# IR2110.net
KiCad netlist of a schematic drawn in Altium Designer
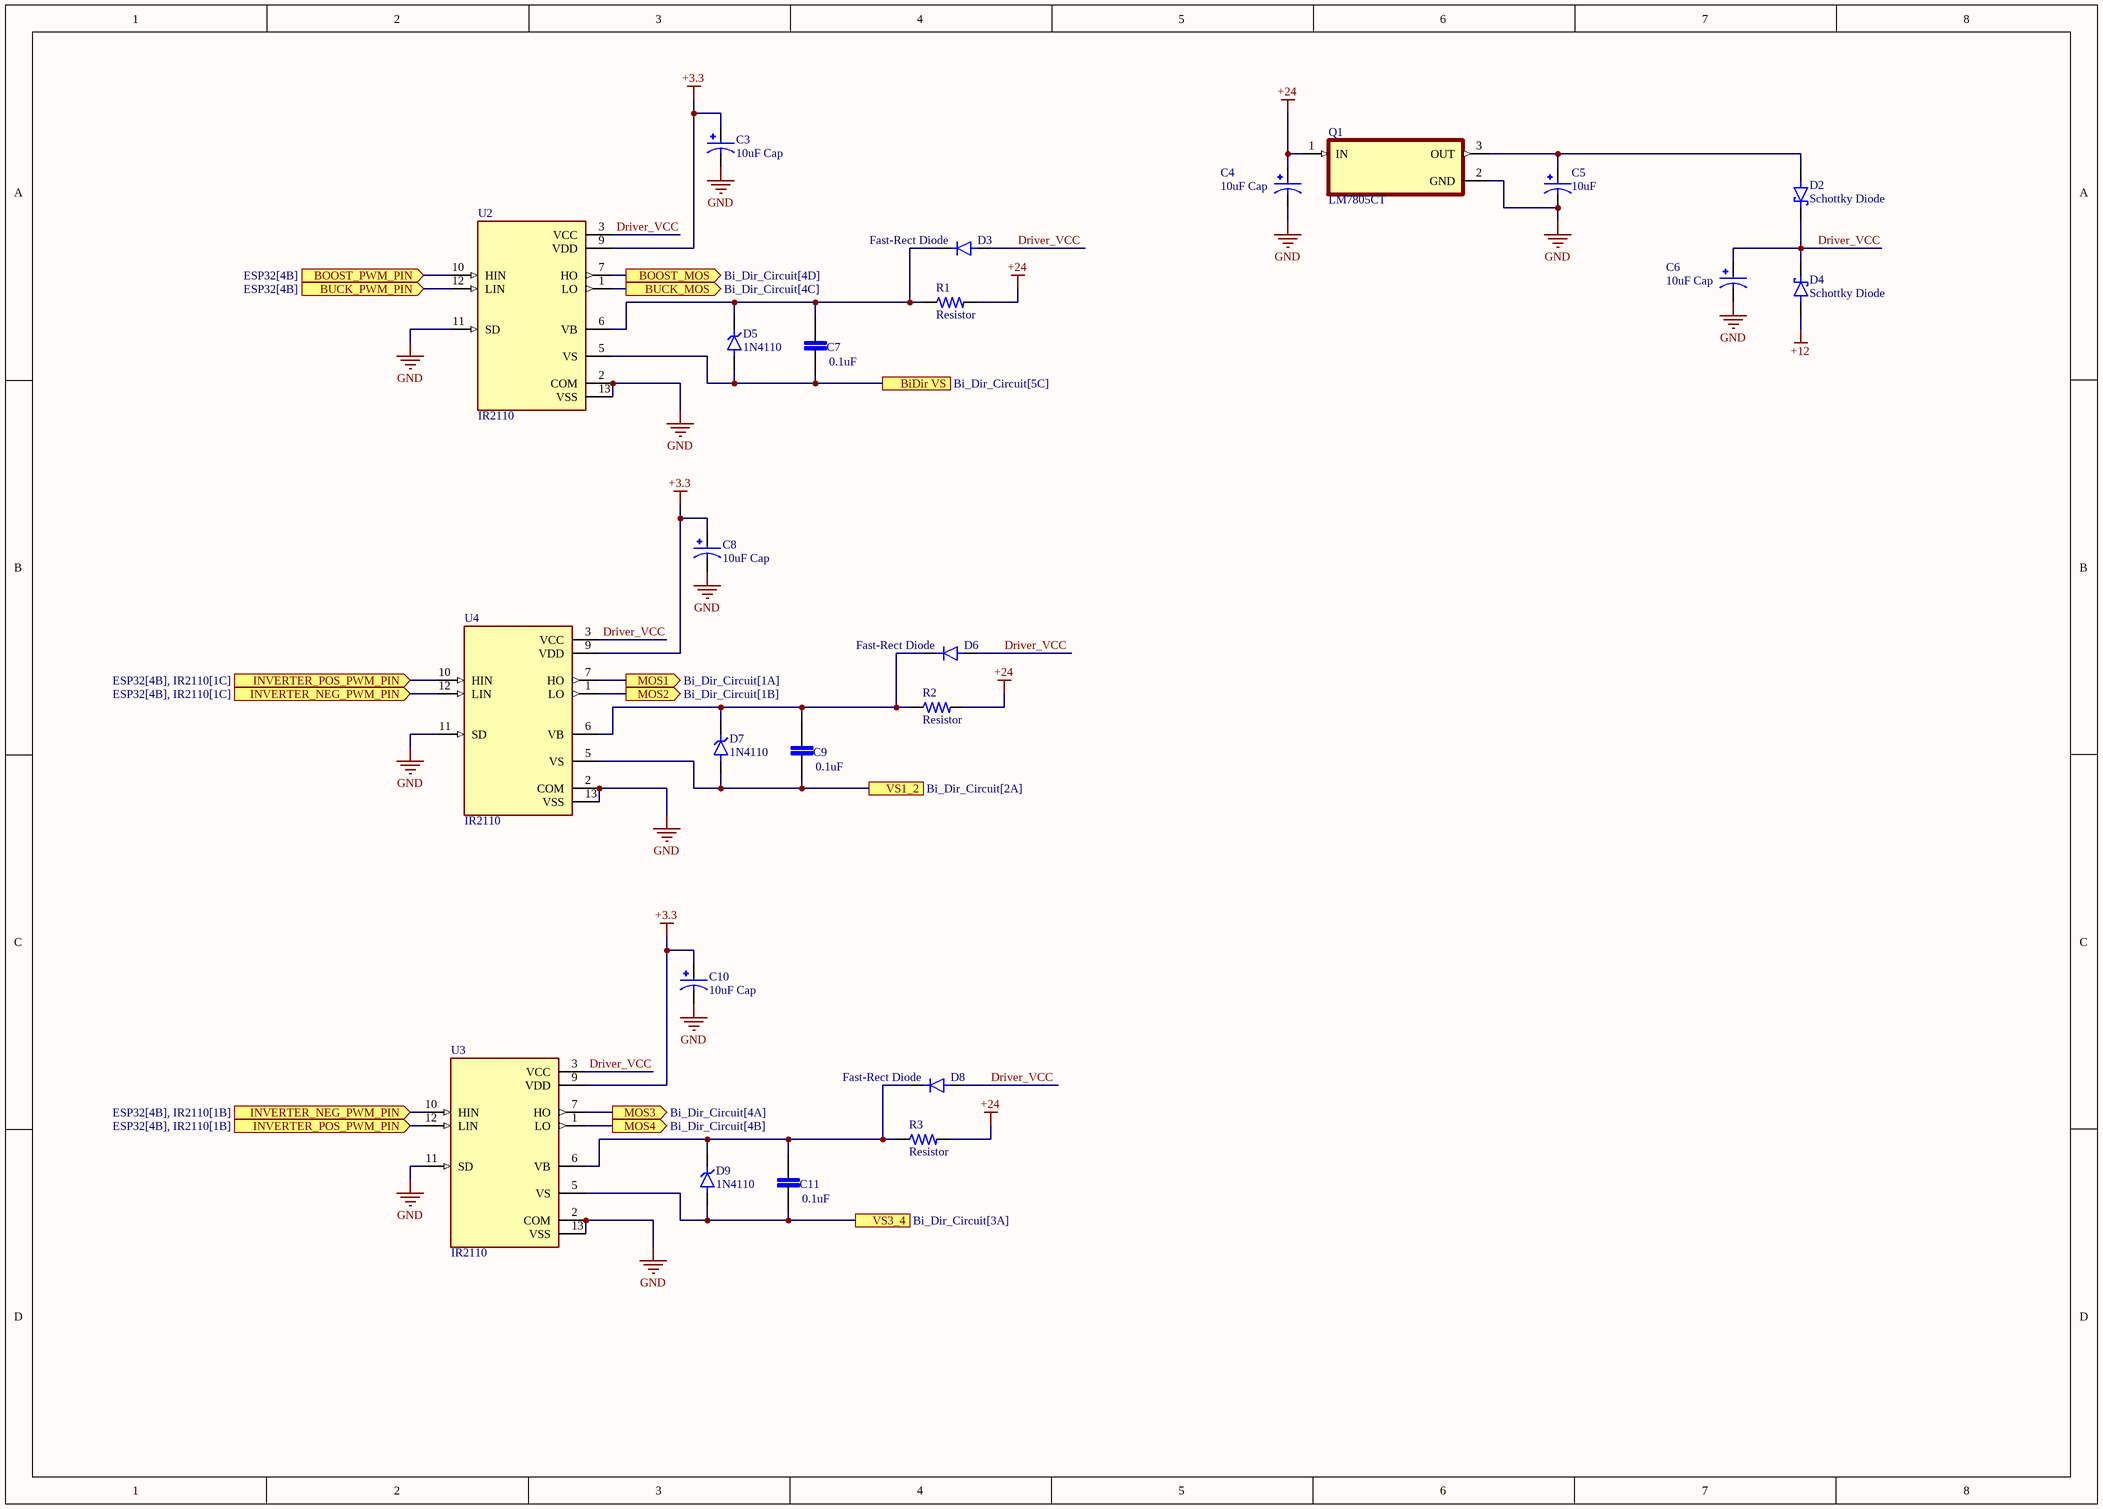
[diagram p0: IR2110.SchDoc]

(export (version "E")
  (design (tool "Eeschema 10.0.6"))
  (components
    (comp (ref "C3")
      (value "10uF Cap")
      (footprint "CAP_10uF")
      (description "CAP ALUM 10UF 20% 50V RADIAL")
      (fields (field (name "MP") "ECE-A1HN100UI") (field (name "MF") "Panasonic"))
      (libsource (lib "MySCH_Library") (part "10uF Cap"))
    )
    (comp (ref "C4")
      (value "10uF Cap")
      (footprint "CAP_10uF")
      (description "CAP ALUM 10UF 20% 50V RADIAL")
      (fields (field (name "MP") "ECE-A1HN100UI") (field (name "MF") "Panasonic"))
      (libsource (lib "MySCH_Library") (part "10uF Cap"))
    )
    (comp (ref "C5")
      (value "10uF")
      (footprint "CAP_10uF")
      (description "CAP ALUM 10UF 20% 50V RADIAL")
      (fields (field (name "MP") "ECE-A1HN100UI") (field (name "MF") "Panasonic"))
      (libsource (lib "MySCH_Library") (part "10uF Cap"))
    )
    (comp (ref "C6")
      (value "10uF Cap")
      (footprint "CAP_10uF")
      (description "CAP ALUM 10UF 20% 50V RADIAL")
      (fields (field (name "MP") "ECE-A1HN100UI") (field (name "MF") "Panasonic"))
      (libsource (lib "MySCH_Library") (part "10uF Cap"))
    )
    (comp (ref "C7")
      (value "0.1uF")
      (footprint "Ceramic Capacitor")
      (fields (field (name "MP") "LD051A121KAB2A") (field (name "MF") "AVX"))
      (libsource (lib "Capacitors Through Hole") (part "Ceramic Capacitor"))
    )
    (comp (ref "C8")
      (value "10uF Cap")
      (footprint "CAP_10uF")
      (description "CAP ALUM 10UF 20% 50V RADIAL")
      (fields (field (name "MP") "ECE-A1HN100UI") (field (name "MF") "Panasonic"))
      (libsource (lib "MySCH_Library") (part "10uF Cap"))
    )
    (comp (ref "C9")
      (value "0.1uF")
      (footprint "Ceramic Capacitor")
      (fields (field (name "MP") "LD051A121KAB2A") (field (name "MF") "AVX"))
      (libsource (lib "Capacitors Through Hole") (part "Ceramic Capacitor"))
    )
    (comp (ref "C10")
      (value "10uF Cap")
      (footprint "CAP_10uF")
      (description "CAP ALUM 10UF 20% 50V RADIAL")
      (fields (field (name "MP") "ECE-A1HN100UI") (field (name "MF") "Panasonic"))
      (libsource (lib "MySCH_Library") (part "10uF Cap"))
    )
    (comp (ref "C11")
      (value "0.1uF")
      (footprint "Ceramic Capacitor")
      (fields (field (name "MP") "LD051A121KAB2A") (field (name "MF") "AVX"))
      (libsource (lib "Capacitors Through Hole") (part "Ceramic Capacitor"))
    )
    (comp (ref "D2")
      (value "Schottky Diode")
      (footprint "Common Trhough Hole")
      (fields (field (name "MF") "Diodes Inc.") (field (name "MP") "1N5817-T"))
      (libsource (lib "Diodes Through Hole") (part "Schottky Diode"))
    )
    (comp (ref "D3")
      (value "Fast-Rect Diode")
      (footprint "Common Trhough Hole")
      (fields (field (name "MF") "NTE Electronics, Inc.") (field (name "MP") "1N4007"))
      (libsource (lib "Diodes Through Hole") (part "Normal Diode"))
    )
    (comp (ref "D4")
      (value "Schottky Diode")
      (footprint "Common Trhough Hole")
      (fields (field (name "MF") "Diodes Inc.") (field (name "MP") "1N5817-T"))
      (libsource (lib "Diodes Through Hole") (part "Schottky Diode"))
    )
    (comp (ref "D5")
      (value "1N4110")
      (footprint "Common Trhough Hole")
      (fields (field (name "MP") "1SMA5926") (field (name "MF") "Taiwan Semiconductor"))
      (libsource (lib "Diodes Through Hole") (part "Zener Diode"))
    )
    (comp (ref "D6")
      (value "Fast-Rect Diode")
      (footprint "Common Trhough Hole")
      (fields (field (name "MF") "NTE Electronics, Inc.") (field (name "MP") "1N4007"))
      (libsource (lib "Diodes Through Hole") (part "Normal Diode"))
    )
    (comp (ref "D7")
      (value "1N4110")
      (footprint "Common Trhough Hole")
      (fields (field (name "MP") "1SMA5926") (field (name "MF") "Taiwan Semiconductor"))
      (libsource (lib "Diodes Through Hole") (part "Zener Diode"))
    )
    (comp (ref "D8")
      (value "Fast-Rect Diode")
      (footprint "Common Trhough Hole")
      (fields (field (name "MF") "NTE Electronics, Inc.") (field (name "MP") "1N4007"))
      (libsource (lib "Diodes Through Hole") (part "Normal Diode"))
    )
    (comp (ref "D9")
      (value "1N4110")
      (footprint "Common Trhough Hole")
      (fields (field (name "MP") "1SMA5926") (field (name "MF") "Taiwan Semiconductor"))
      (libsource (lib "Diodes Through Hole") (part "Zener Diode"))
    )
    (comp (ref "Q1")
      (value "LM7805CT")
      (footprint "LM7805CT")
      (fields (field (name "MP") "LM7805CT/NOPB"))
      (libsource (lib "Voltage Regulators Through Hole") (part "LM7805CT"))
    )
    (comp (ref "R1")
      (value "Resistor")
      (footprint "Resistor_Through Hole")
      (fields
        (field (name "MP") "2-2176053-0")
        (field (name "TOLERANCE") "1%")
        (field (name "MF") "TE Connectivity")
      )
      (libsource (lib "Resistors Through Hole") (part "Resistor"))
    )
    (comp (ref "R2")
      (value "Resistor")
      (footprint "Resistor_Through Hole")
      (fields
        (field (name "MP") "2-2176053-0")
        (field (name "TOLERANCE") "1%")
        (field (name "MF") "TE Connectivity")
      )
      (libsource (lib "Resistors Through Hole") (part "Resistor"))
    )
    (comp (ref "R3")
      (value "Resistor")
      (footprint "Resistor_Through Hole")
      (fields
        (field (name "MP") "2-2176053-0")
        (field (name "TOLERANCE") "1%")
        (field (name "MF") "TE Connectivity")
      )
      (libsource (lib "Resistors Through Hole") (part "Resistor"))
    )
    (comp (ref "U2")
      (value "IR2110")
      (footprint "IR2110")
      (description "Half-Bridge Gate Driver IC Non-Inverting 16-SOIC")
      (fields (field (name "MF") "Infineon"))
      (libsource (lib "MySCH_Library") (part "IR2110"))
    )
    (comp (ref "U3")
      (value "IR2110")
      (footprint "IR2110")
      (description "Half-Bridge Gate Driver IC Non-Inverting 16-SOIC")
      (fields (field (name "MF") "Infineon"))
      (libsource (lib "MySCH_Library") (part "IR2110"))
    )
    (comp (ref "U4")
      (value "IR2110")
      (footprint "IR2110")
      (description "Half-Bridge Gate Driver IC Non-Inverting 16-SOIC")
      (fields (field (name "MF") "Infineon"))
      (libsource (lib "MySCH_Library") (part "IR2110"))
    )
  )
  (nets
    (net (code "1") (name "+3.3") (class "Default")
      (node (ref "C10") (pin "P") (pinfunction "P_P") (pintype "passive"))
      (node (ref "C3") (pin "P") (pinfunction "P_P") (pintype "passive"))
      (node (ref "C8") (pin "P") (pinfunction "P_P") (pintype "passive"))
      (node (ref "U2") (pin "9") (pinfunction "VDD_9") (pintype "power_in"))
      (node (ref "U3") (pin "9") (pinfunction "VDD_9") (pintype "power_in"))
      (node (ref "U4") (pin "9") (pinfunction "VDD_9") (pintype "power_in"))
    )
    (net (code "2") (name "+12") (class "Default")
      (node (ref "D4") (pin "2") (pinfunction "A_2") (pintype "passive"))
    )
    (net (code "3") (name "+24") (class "Default")
      (node (ref "C4") (pin "P") (pinfunction "P_P") (pintype "passive"))
      (node (ref "Q1") (pin "1") (pinfunction "IN_1") (pintype "input"))
      (node (ref "R1") (pin "2") (pinfunction "2_2") (pintype "passive"))
      (node (ref "R2") (pin "2") (pinfunction "2_2") (pintype "passive"))
      (node (ref "R3") (pin "2") (pinfunction "2_2") (pintype "passive"))
    )
    (net (code "4") (name "/BOOST_MOS") (class "Default")
      (node (ref "U2") (pin "7") (pinfunction "HO_7") (pintype "output"))
    )
    (net (code "5") (name "/BOOST_PWM_PIN") (class "Default")
      (node (ref "U2") (pin "10") (pinfunction "HIN_10") (pintype "input"))
    )
    (net (code "6") (name "/BUCK_MOS") (class "Default")
      (node (ref "U2") (pin "1") (pinfunction "LO_1") (pintype "output"))
    )
    (net (code "7") (name "/BUCK_PWM_PIN") (class "Default")
      (node (ref "U2") (pin "12") (pinfunction "LIN_12") (pintype "input"))
    )
    (net (code "8") (name "/BiDir VS") (class "Default")
      (node (ref "C7") (pin "1") (pinfunction "1_1") (pintype "passive"))
      (node (ref "D5") (pin "2") (pinfunction "A_2") (pintype "passive"))
      (node (ref "U2") (pin "5") (pinfunction "VS_5") (pintype "passive"))
    )
    (net (code "9") (name "/Driver_VCC") (class "Default")
      (node (ref "C6") (pin "P") (pinfunction "P_P") (pintype "passive"))
      (node (ref "D2") (pin "1") (pinfunction "K_1") (pintype "passive"))
      (node (ref "D3") (pin "2") (pinfunction "A_2") (pintype "passive"))
      (node (ref "D4") (pin "1") (pinfunction "K_1") (pintype "passive"))
      (node (ref "D6") (pin "2") (pinfunction "A_2") (pintype "passive"))
      (node (ref "D8") (pin "2") (pinfunction "A_2") (pintype "passive"))
      (node (ref "U2") (pin "3") (pinfunction "VCC_3") (pintype "power_in"))
      (node (ref "U3") (pin "3") (pinfunction "VCC_3") (pintype "power_in"))
      (node (ref "U4") (pin "3") (pinfunction "VCC_3") (pintype "power_in"))
    )
    (net (code "10") (name "/INVERTER_NEG_PWM_PIN") (class "Default")
      (node (ref "U3") (pin "10") (pinfunction "HIN_10") (pintype "input"))
      (node (ref "U4") (pin "12") (pinfunction "LIN_12") (pintype "input"))
    )
    (net (code "11") (name "/INVERTER_POS_PWM_PIN") (class "Default")
      (node (ref "U3") (pin "12") (pinfunction "LIN_12") (pintype "input"))
      (node (ref "U4") (pin "10") (pinfunction "HIN_10") (pintype "input"))
    )
    (net (code "12") (name "/MOS1") (class "Default")
      (node (ref "U4") (pin "7") (pinfunction "HO_7") (pintype "output"))
    )
    (net (code "13") (name "/MOS2") (class "Default")
      (node (ref "U4") (pin "1") (pinfunction "LO_1") (pintype "output"))
    )
    (net (code "14") (name "/MOS3") (class "Default")
      (node (ref "U3") (pin "7") (pinfunction "HO_7") (pintype "output"))
    )
    (net (code "15") (name "/MOS4") (class "Default")
      (node (ref "U3") (pin "1") (pinfunction "LO_1") (pintype "output"))
    )
    (net (code "16") (name "/VS1_2") (class "Default")
      (node (ref "C9") (pin "1") (pinfunction "1_1") (pintype "passive"))
      (node (ref "D7") (pin "2") (pinfunction "A_2") (pintype "passive"))
      (node (ref "U4") (pin "5") (pinfunction "VS_5") (pintype "passive"))
    )
    (net (code "17") (name "/VS3_4") (class "Default")
      (node (ref "C11") (pin "1") (pinfunction "1_1") (pintype "passive"))
      (node (ref "D9") (pin "2") (pinfunction "A_2") (pintype "passive"))
      (node (ref "U3") (pin "5") (pinfunction "VS_5") (pintype "passive"))
    )
    (net (code "18") (name "GND") (class "Default")
      (node (ref "C10") (pin "N") (pinfunction "N_N") (pintype "passive"))
      (node (ref "C3") (pin "N") (pinfunction "N_N") (pintype "passive"))
      (node (ref "C4") (pin "N") (pinfunction "N_N") (pintype "passive"))
      (node (ref "C5") (pin "N") (pinfunction "N_N") (pintype "passive"))
      (node (ref "C6") (pin "N") (pinfunction "N_N") (pintype "passive"))
      (node (ref "C8") (pin "N") (pinfunction "N_N") (pintype "passive"))
      (node (ref "Q1") (pin "2") (pinfunction "GND_2") (pintype "power_in"))
      (node (ref "U2") (pin "11") (pinfunction "SD_11") (pintype "input"))
      (node (ref "U2") (pin "13") (pinfunction "VSS_13") (pintype "power_in"))
      (node (ref "U2") (pin "2") (pinfunction "COM_2") (pintype "power_in"))
      (node (ref "U3") (pin "11") (pinfunction "SD_11") (pintype "input"))
      (node (ref "U3") (pin "13") (pinfunction "VSS_13") (pintype "power_in"))
      (node (ref "U3") (pin "2") (pinfunction "COM_2") (pintype "power_in"))
      (node (ref "U4") (pin "11") (pinfunction "SD_11") (pintype "input"))
      (node (ref "U4") (pin "13") (pinfunction "VSS_13") (pintype "power_in"))
      (node (ref "U4") (pin "2") (pinfunction "COM_2") (pintype "power_in"))
    )
    (net (code "19") (name "Net-(D2-A)") (class "Default")
      (node (ref "C5") (pin "P") (pinfunction "P_P") (pintype "passive"))
      (node (ref "D2") (pin "2") (pinfunction "A_2") (pintype "passive"))
      (node (ref "Q1") (pin "3") (pinfunction "OUT_3") (pintype "output"))
    )
    (net (code "20") (name "Net-(D3-K)") (class "Default")
      (node (ref "C7") (pin "2") (pinfunction "2_2") (pintype "passive"))
      (node (ref "D3") (pin "1") (pinfunction "K_1") (pintype "passive"))
      (node (ref "D5") (pin "1") (pinfunction "K_1") (pintype "passive"))
      (node (ref "R1") (pin "1") (pinfunction "1_1") (pintype "passive"))
      (node (ref "U2") (pin "6") (pinfunction "VB_6") (pintype "passive"))
    )
    (net (code "21") (name "Net-(D6-K)") (class "Default")
      (node (ref "C9") (pin "2") (pinfunction "2_2") (pintype "passive"))
      (node (ref "D6") (pin "1") (pinfunction "K_1") (pintype "passive"))
      (node (ref "D7") (pin "1") (pinfunction "K_1") (pintype "passive"))
      (node (ref "R2") (pin "1") (pinfunction "1_1") (pintype "passive"))
      (node (ref "U4") (pin "6") (pinfunction "VB_6") (pintype "passive"))
    )
    (net (code "22") (name "Net-(D8-K)") (class "Default")
      (node (ref "C11") (pin "2") (pinfunction "2_2") (pintype "passive"))
      (node (ref "D8") (pin "1") (pinfunction "K_1") (pintype "passive"))
      (node (ref "D9") (pin "1") (pinfunction "K_1") (pintype "passive"))
      (node (ref "R3") (pin "1") (pinfunction "1_1") (pintype "passive"))
      (node (ref "U3") (pin "6") (pinfunction "VB_6") (pintype "passive"))
    )
  )
)
